# Modified-Pro-Mini.net
KiCad netlist of a schematic drawn in EAGLE
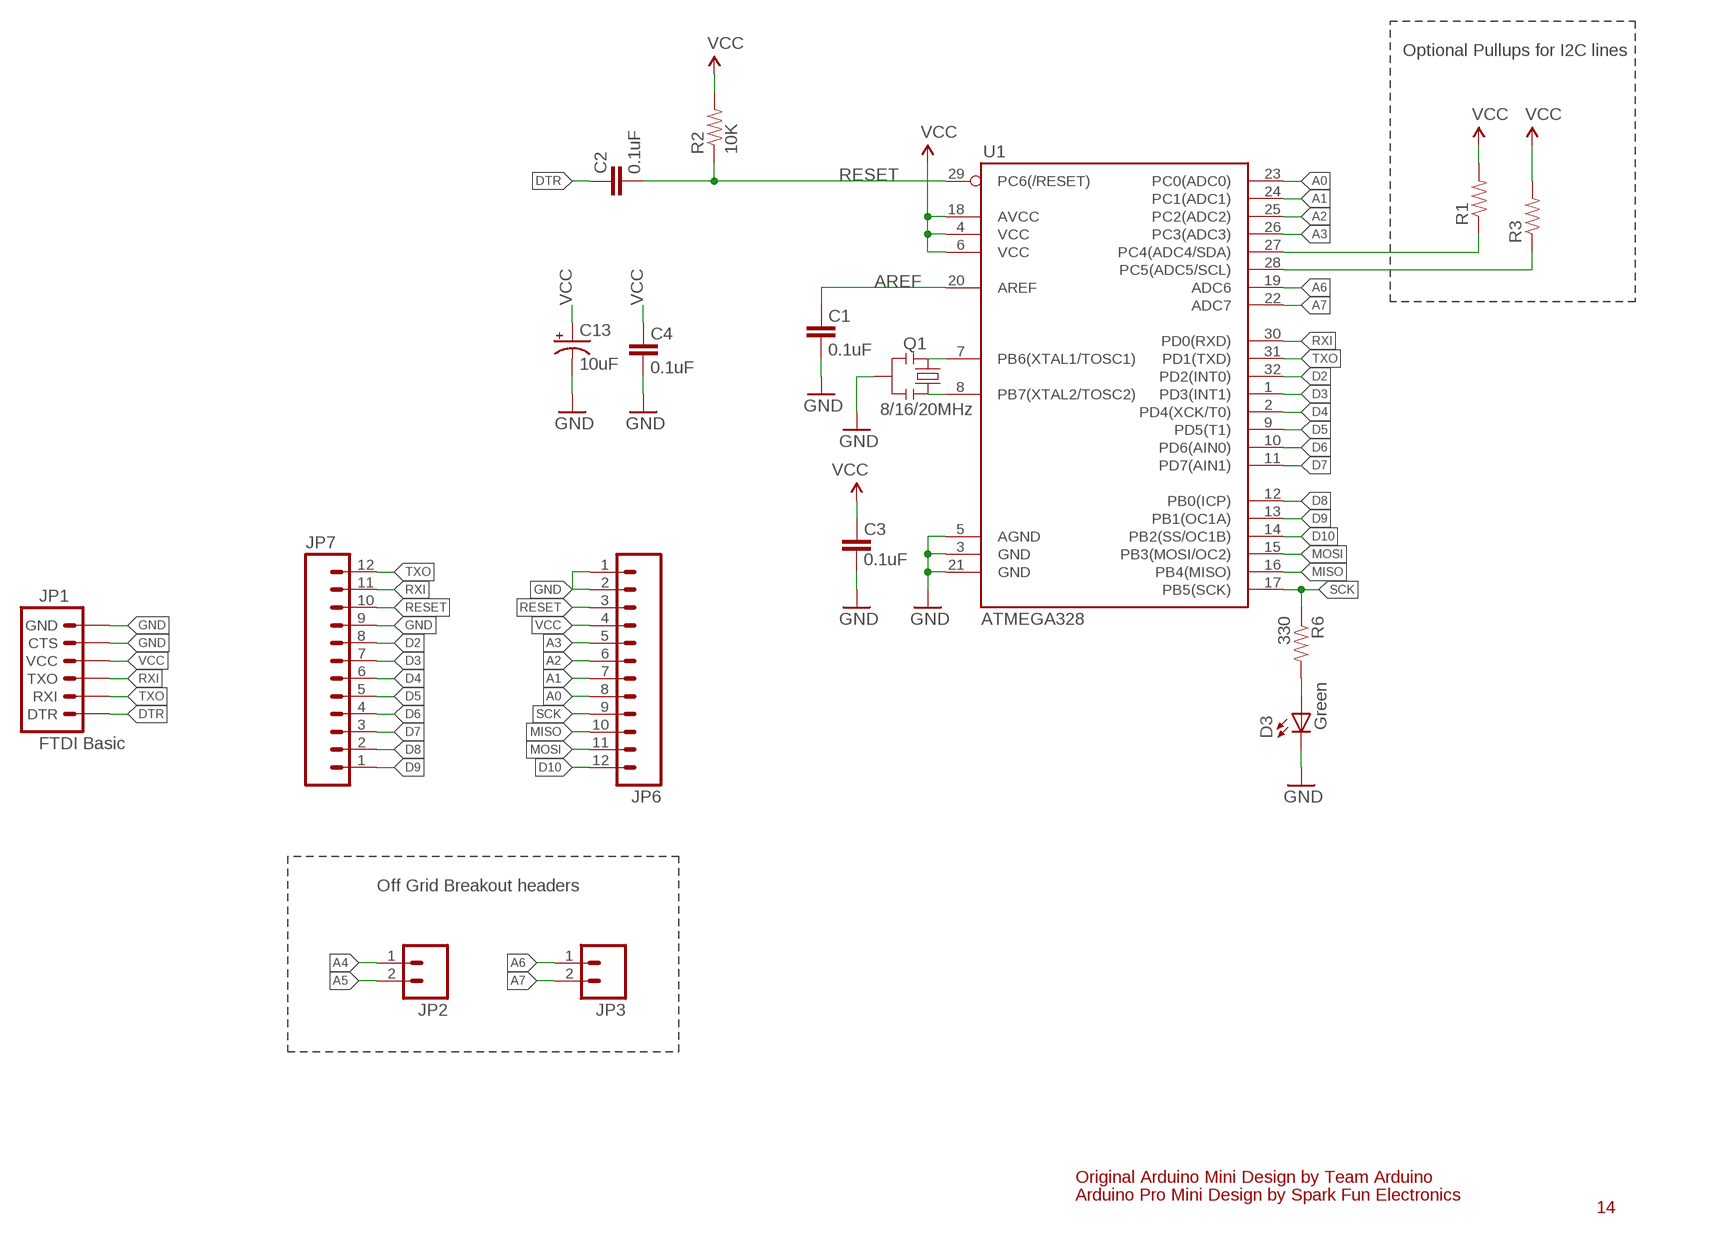
[diagram p0: schematic, sheet 1]

(export (version "E")
  (design (tool "Eeschema 10.0.6"))
  (components
    (comp (ref "C1")
      (value "0.1uF")
      (footprint "eagle-import:0603-CAP")
      (libsource (lib "eagle-import") (part "CAP0603-CAP"))
    )
    (comp (ref "C2")
      (value "0.1uF")
      (footprint "eagle-import:0603-CAP")
      (libsource (lib "eagle-import") (part "CAP0603-CAP"))
    )
    (comp (ref "C3")
      (value "0.1uF")
      (footprint "eagle-import:0603-CAP")
      (libsource (lib "eagle-import") (part "CAP0603-CAP"))
    )
    (comp (ref "C4")
      (value "0.1uF")
      (footprint "eagle-import:0603-CAP")
      (libsource (lib "eagle-import") (part "CAP0603-CAP"))
    )
    (comp (ref "C13")
      (value "10uF")
      (footprint "eagle-import:EIA3216")
      (libsource (lib "eagle-import") (part "CAP_POL1206"))
    )
    (comp (ref "D3")
      (value "Green")
      (footprint "eagle-import:0603-LED-ALT1")
      (libsource (lib "eagle-import") (part "LED"))
    )
    (comp (ref "JP1")
      (value "FTDI Basic")
      (footprint "eagle-import:1X06")
      (libsource (lib "eagle-import") (part "ARDUINO_SERIAL_PROGRAMPTH"))
    )
    (comp (ref "JP2")
      (value "M02PTH")
      (footprint "eagle-import:1X02")
      (libsource (lib "eagle-import") (part "M02PTH"))
    )
    (comp (ref "JP3")
      (value "M02PTH")
      (footprint "eagle-import:1X02")
      (libsource (lib "eagle-import") (part "M02PTH"))
    )
    (comp (ref "JP6")
      (value "M12PTH")
      (footprint "eagle-import:1X12")
      (libsource (lib "eagle-import") (part "M12PTH"))
    )
    (comp (ref "JP7")
      (value "M12PTH")
      (footprint "eagle-import:1X12")
      (libsource (lib "eagle-import") (part "M12PTH"))
    )
    (comp (ref "Q1")
      (value "8/16/20MHz")
      (footprint "eagle-import:RESONATOR-SMD-1_1")
      (libsource (lib "eagle-import") (part "RESONATOR1{colon}1"))
    )
    (comp (ref "R1")
      (value "RESISTOR0603-RES")
      (footprint "eagle-import:0603-RES")
      (libsource (lib "eagle-import") (part "RESISTOR0603-RES"))
    )
    (comp (ref "R2")
      (value "10K")
      (footprint "eagle-import:0603-RES")
      (libsource (lib "eagle-import") (part "RESISTOR0603-RES"))
    )
    (comp (ref "R3")
      (value "RESISTOR0603-RES")
      (footprint "eagle-import:0603-RES")
      (libsource (lib "eagle-import") (part "RESISTOR0603-RES"))
    )
    (comp (ref "R6")
      (value "330")
      (footprint "eagle-import:0603-RES")
      (libsource (lib "eagle-import") (part "RESISTOR0603-RES"))
    )
    (comp (ref "U1")
      (value "ATMEGA328")
      (footprint "eagle-import:TQFP32-08")
      (libsource (lib "eagle-import") (part "ATMEGA168"))
    )
  )
  (nets
    (net (code "1") (name "/AREF") (class "Default")
      (node (ref "C1") (pin "2") (pinfunction "2_2") (pintype "passive"))
      (node (ref "U1") (pin "20") (pinfunction "AREF_20") (pintype "bidirectional"))
    )
    (net (code "2") (name "A0") (class "Default")
      (node (ref "JP6") (pin "8") (pinfunction "8_8") (pintype "passive"))
      (node (ref "U1") (pin "23") (pinfunction "PC0(ADC0)_23") (pintype "bidirectional"))
    )
    (net (code "3") (name "A1") (class "Default")
      (node (ref "JP6") (pin "7") (pinfunction "7_7") (pintype "passive"))
      (node (ref "U1") (pin "24") (pinfunction "PC1(ADC1)_24") (pintype "bidirectional"))
    )
    (net (code "4") (name "A2") (class "Default")
      (node (ref "JP6") (pin "6") (pinfunction "6_6") (pintype "passive"))
      (node (ref "U1") (pin "25") (pinfunction "PC2(ADC2)_25") (pintype "bidirectional"))
    )
    (net (code "5") (name "A3") (class "Default")
      (node (ref "JP6") (pin "5") (pinfunction "5_5") (pintype "passive"))
      (node (ref "U1") (pin "26") (pinfunction "PC3(ADC3)_26") (pintype "bidirectional"))
    )
    (net (code "6") (name "A4") (class "Default")
      (node (ref "JP2") (pin "1") (pinfunction "1_1") (pintype "passive"))
      (node (ref "R1") (pin "1") (pinfunction "1_1") (pintype "passive"))
      (node (ref "U1") (pin "27") (pinfunction "PC4(ADC4/SDA)_27") (pintype "bidirectional"))
    )
    (net (code "7") (name "A5") (class "Default")
      (node (ref "JP2") (pin "2") (pinfunction "2_2") (pintype "passive"))
      (node (ref "R3") (pin "1") (pinfunction "1_1") (pintype "passive"))
      (node (ref "U1") (pin "28") (pinfunction "PC5(ADC5/SCL)_28") (pintype "bidirectional"))
    )
    (net (code "8") (name "A6") (class "Default")
      (node (ref "JP3") (pin "1") (pinfunction "1_1") (pintype "passive"))
      (node (ref "U1") (pin "19") (pinfunction "ADC6_19") (pintype "bidirectional"))
    )
    (net (code "9") (name "A7") (class "Default")
      (node (ref "JP3") (pin "2") (pinfunction "2_2") (pintype "passive"))
      (node (ref "U1") (pin "22") (pinfunction "ADC7_22") (pintype "bidirectional"))
    )
    (net (code "10") (name "D2") (class "Default")
      (node (ref "JP7") (pin "8") (pinfunction "8_8") (pintype "passive"))
      (node (ref "U1") (pin "32") (pinfunction "PD2(INT0)_32") (pintype "bidirectional"))
    )
    (net (code "11") (name "D3") (class "Default")
      (node (ref "JP7") (pin "7") (pinfunction "7_7") (pintype "passive"))
      (node (ref "U1") (pin "1") (pinfunction "PD3(INT1)_1") (pintype "bidirectional"))
    )
    (net (code "12") (name "D4") (class "Default")
      (node (ref "JP7") (pin "6") (pinfunction "6_6") (pintype "passive"))
      (node (ref "U1") (pin "2") (pinfunction "PD4(XCK/T0)_2") (pintype "bidirectional"))
    )
    (net (code "13") (name "D5") (class "Default")
      (node (ref "JP7") (pin "5") (pinfunction "5_5") (pintype "passive"))
      (node (ref "U1") (pin "9") (pinfunction "PD5(T1)_9") (pintype "bidirectional"))
    )
    (net (code "14") (name "D6") (class "Default")
      (node (ref "JP7") (pin "4") (pinfunction "4_4") (pintype "passive"))
      (node (ref "U1") (pin "10") (pinfunction "PD6(AIN0)_10") (pintype "bidirectional"))
    )
    (net (code "15") (name "D7") (class "Default")
      (node (ref "JP7") (pin "3") (pinfunction "3_3") (pintype "passive"))
      (node (ref "U1") (pin "11") (pinfunction "PD7(AIN1)_11") (pintype "bidirectional"))
    )
    (net (code "16") (name "D8") (class "Default")
      (node (ref "JP7") (pin "2") (pinfunction "2_2") (pintype "passive"))
      (node (ref "U1") (pin "12") (pinfunction "PB0(ICP)_12") (pintype "bidirectional"))
    )
    (net (code "17") (name "D9") (class "Default")
      (node (ref "JP7") (pin "1") (pinfunction "1_1") (pintype "passive"))
      (node (ref "U1") (pin "13") (pinfunction "PB1(OC1A)_13") (pintype "bidirectional"))
    )
    (net (code "18") (name "D10") (class "Default")
      (node (ref "JP6") (pin "12") (pinfunction "12_12") (pintype "passive"))
      (node (ref "U1") (pin "14") (pinfunction "PB2(SS/OC1B)_14") (pintype "bidirectional"))
    )
    (net (code "19") (name "DTR") (class "Default")
      (node (ref "C2") (pin "2") (pinfunction "2_2") (pintype "passive"))
      (node (ref "JP1") (pin "1") (pinfunction "DTR_1") (pintype "passive"))
    )
    (net (code "20") (name "GND") (class "Default")
      (node (ref "C1") (pin "1") (pinfunction "1_1") (pintype "passive"))
      (node (ref "C13") (pin "C") (pinfunction "-_C") (pintype "passive"))
      (node (ref "C3") (pin "1") (pinfunction "1_1") (pintype "passive"))
      (node (ref "C4") (pin "1") (pinfunction "1_1") (pintype "passive"))
      (node (ref "D3") (pin "C") (pinfunction "C_C") (pintype "passive"))
      (node (ref "JP1") (pin "5") (pinfunction "CTS_5") (pintype "passive"))
      (node (ref "JP1") (pin "6") (pinfunction "GND_6") (pintype "passive"))
      (node (ref "JP6") (pin "1") (pinfunction "1_1") (pintype "passive"))
      (node (ref "JP6") (pin "2") (pinfunction "2_2") (pintype "passive"))
      (node (ref "JP7") (pin "9") (pinfunction "9_9") (pintype "passive"))
      (node (ref "Q1") (pin "2") (pinfunction "2_2") (pintype "passive"))
      (node (ref "U1") (pin "21") (pinfunction "GND_21") (pintype "bidirectional"))
      (node (ref "U1") (pin "3") (pinfunction "GND_3") (pintype "bidirectional"))
      (node (ref "U1") (pin "5") (pinfunction "AGND_5") (pintype "bidirectional"))
    )
    (net (code "21") (name "MISO") (class "Default")
      (node (ref "JP6") (pin "10") (pinfunction "10_10") (pintype "passive"))
      (node (ref "U1") (pin "16") (pinfunction "PB4(MISO)_16") (pintype "bidirectional"))
    )
    (net (code "22") (name "MOSI") (class "Default")
      (node (ref "JP6") (pin "11") (pinfunction "11_11") (pintype "passive"))
      (node (ref "U1") (pin "15") (pinfunction "PB3(MOSI/OC2)_15") (pintype "bidirectional"))
    )
    (net (code "23") (name "Net-(D3-PadA)") (class "Default")
      (node (ref "D3") (pin "A") (pinfunction "A_A") (pintype "passive"))
      (node (ref "R6") (pin "2") (pinfunction "2_2") (pintype "passive"))
    )
    (net (code "24") (name "Net-(U1-PB6(XTAL1{slash}TOSC1))") (class "Default")
      (node (ref "Q1") (pin "1") (pinfunction "1_1") (pintype "passive"))
      (node (ref "U1") (pin "7") (pinfunction "PB6(XTAL1/TOSC1)_7") (pintype "bidirectional"))
    )
    (net (code "25") (name "Net-(U1-PB7(XTAL2{slash}TOSC2))") (class "Default")
      (node (ref "Q1") (pin "3") (pinfunction "3_3") (pintype "passive"))
      (node (ref "U1") (pin "8") (pinfunction "PB7(XTAL2/TOSC2)_8") (pintype "bidirectional"))
    )
    (net (code "26") (name "RESET") (class "Default")
      (node (ref "C2") (pin "1") (pinfunction "1_1") (pintype "passive"))
      (node (ref "JP6") (pin "3") (pinfunction "3_3") (pintype "passive"))
      (node (ref "JP7") (pin "10") (pinfunction "10_10") (pintype "passive"))
      (node (ref "R2") (pin "1") (pinfunction "1_1") (pintype "passive"))
      (node (ref "U1") (pin "29") (pinfunction "PC6(/RESET)_29") (pintype "bidirectional"))
    )
    (net (code "27") (name "RXI") (class "Default")
      (node (ref "JP1") (pin "3") (pinfunction "TXO_3") (pintype "passive"))
      (node (ref "JP7") (pin "11") (pinfunction "11_11") (pintype "passive"))
      (node (ref "U1") (pin "30") (pinfunction "PD0(RXD)_30") (pintype "bidirectional"))
    )
    (net (code "28") (name "SCK") (class "Default")
      (node (ref "JP6") (pin "9") (pinfunction "9_9") (pintype "passive"))
      (node (ref "R6") (pin "1") (pinfunction "1_1") (pintype "passive"))
      (node (ref "U1") (pin "17") (pinfunction "PB5(SCK)_17") (pintype "bidirectional"))
    )
    (net (code "29") (name "TXO") (class "Default")
      (node (ref "JP1") (pin "2") (pinfunction "RXI_2") (pintype "passive"))
      (node (ref "JP7") (pin "12") (pinfunction "12_12") (pintype "passive"))
      (node (ref "U1") (pin "31") (pinfunction "PD1(TXD)_31") (pintype "bidirectional"))
    )
    (net (code "30") (name "VCC") (class "Default")
      (node (ref "C13") (pin "A") (pinfunction "+_A") (pintype "passive"))
      (node (ref "C3") (pin "2") (pinfunction "2_2") (pintype "passive"))
      (node (ref "C4") (pin "2") (pinfunction "2_2") (pintype "passive"))
      (node (ref "JP1") (pin "4") (pinfunction "VCC_4") (pintype "passive"))
      (node (ref "JP6") (pin "4") (pinfunction "4_4") (pintype "passive"))
      (node (ref "R1") (pin "2") (pinfunction "2_2") (pintype "passive"))
      (node (ref "R2") (pin "2") (pinfunction "2_2") (pintype "passive"))
      (node (ref "R3") (pin "2") (pinfunction "2_2") (pintype "passive"))
      (node (ref "U1") (pin "18") (pinfunction "AVCC_18") (pintype "bidirectional"))
      (node (ref "U1") (pin "4") (pinfunction "VCC_4") (pintype "bidirectional"))
      (node (ref "U1") (pin "6") (pinfunction "VCC_6") (pintype "bidirectional"))
    )
  )
)
